# easyedainfo.net
KiCad netlist of a schematic drawn in EasyEDA
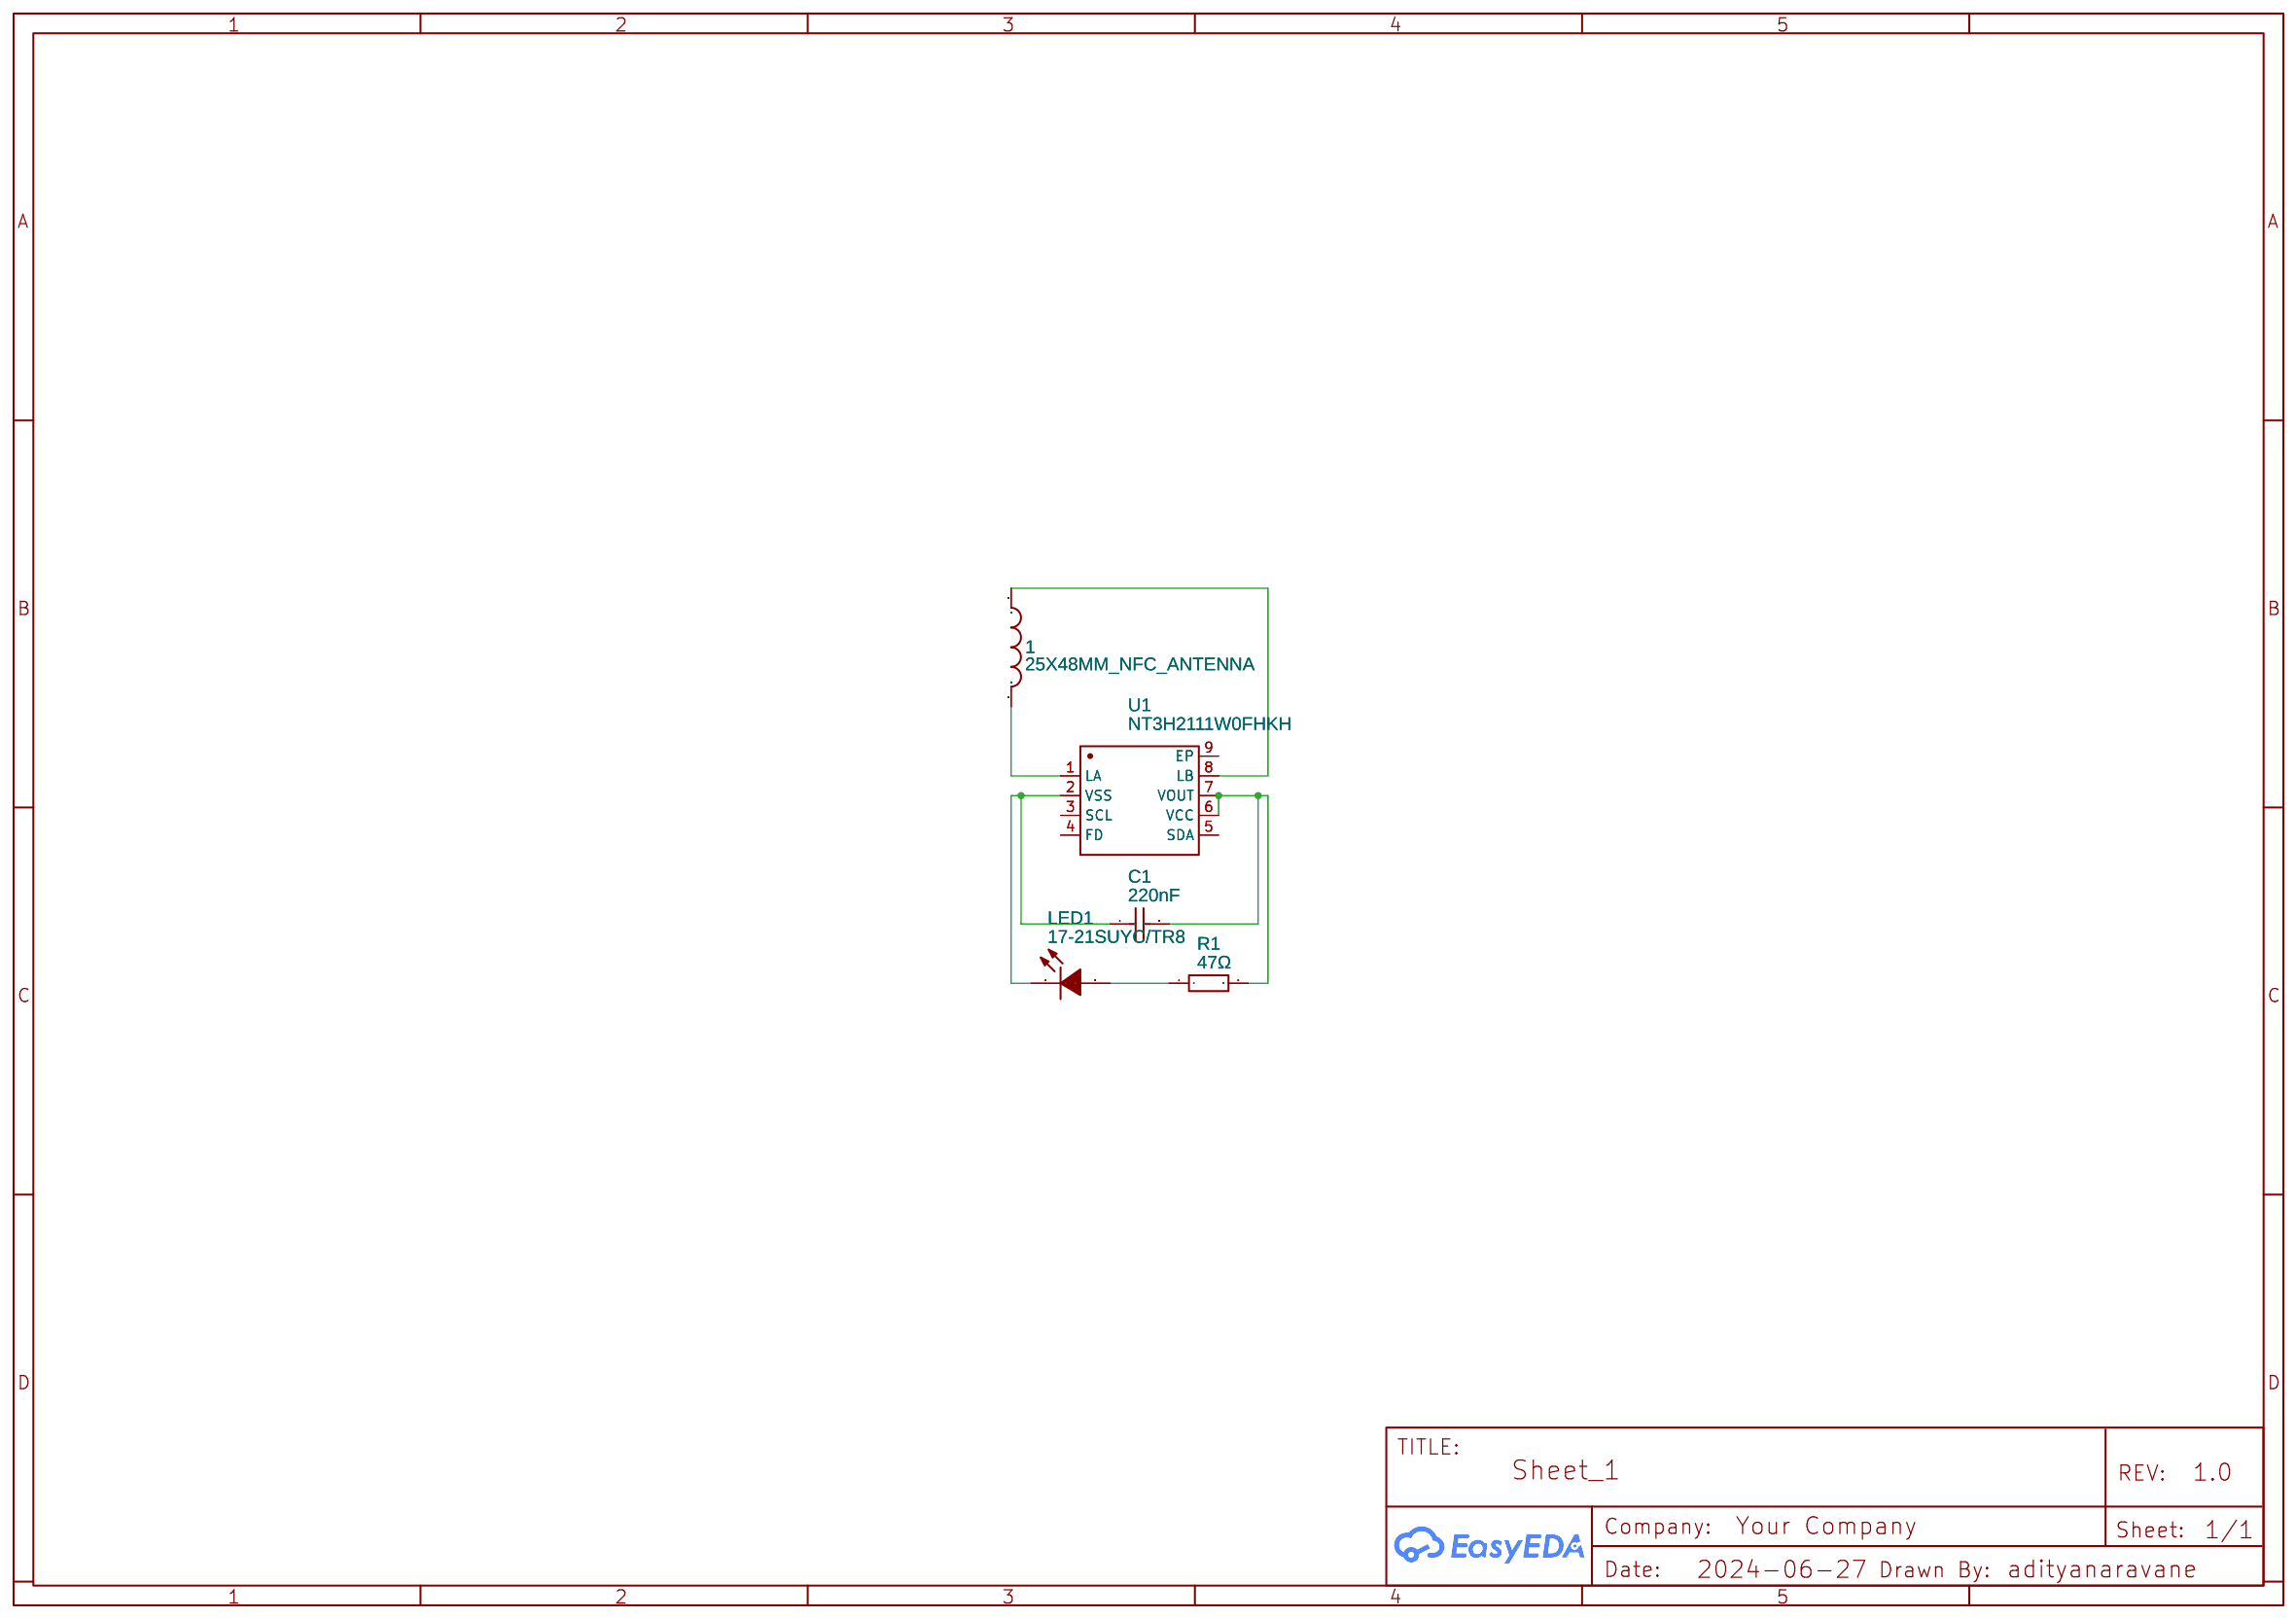
[diagram p0: schematic sheet]

(export (version "E")
  (design (tool "Eeschema 10.0.6"))
  (components
    (comp (ref "1") (value "25X48MM_NFC_ANTENNA") (libsource (lib "") (part "25X48MM_NFC_ANTENNA")))
    (comp (ref "C1")
      (value "220nF")
      (fields
        (field (name "Manufacturer Part") "CL10B224KA8NNNC")
        (field (name "Manufacturer") "SAMSUNG(三星)")
      )
      (libsource (lib "") (part "CL10B224KA8NNNC"))
    )
    (comp (ref "LED1")
      (value "17-21SUYC/TR8")
      (fields (field (name "Manufacturer Part") "KT-0805黄灯") (field (name "Manufacturer") "KENTO"))
      (libsource (lib "") (part "17-21SUYC/TR8"))
    )
    (comp (ref "R1")
      (value "47Ω")
      (fields
        (field (name "Manufacturer Part") "0603WAF470JT5E")
        (field (name "Manufacturer") "UNI-ROYAL(厚声)")
      )
      (libsource (lib "") (part "0603WAF470JT5E"))
    )
    (comp (ref "U1")
      (value "NT3H2111W0FHKH")
      (fields (field (name "Manufacturer") "NXP(恩智浦)"))
      (libsource (lib "") (part "NT3H2111W0FHKH"))
    )
  )
  (nets
    (net (code "1") (name "Net-(LED1-+)") (class "Default")
      (node (ref "LED1") (pin "1") (pinfunction "+_1") (pintype "unspecified"))
      (node (ref "R1") (pin "1") (pinfunction "1_1") (pintype "input"))
    )
    (net (code "2") (name "Net-(LED1--)") (class "Default")
      (node (ref "C1") (pin "1") (pinfunction "1_1") (pintype "input"))
      (node (ref "LED1") (pin "2") (pinfunction "-_2") (pintype "unspecified"))
      (node (ref "U1") (pin "2") (pinfunction "VSS_2") (pintype "unspecified"))
    )
    (net (code "3") (name "Net-(U1-LA)") (class "Default")
      (node (ref "1") (pin "P$2") (pinfunction "P$2_P$2") (pintype "bidirectional"))
      (node (ref "U1") (pin "1") (pinfunction "LA_1") (pintype "unspecified"))
    )
    (net (code "4") (name "Net-(U1-LB)") (class "Default")
      (node (ref "1") (pin "P$1") (pinfunction "P$1_P$1") (pintype "bidirectional"))
      (node (ref "U1") (pin "8") (pinfunction "LB_8") (pintype "unspecified"))
    )
    (net (code "5") (name "Net-(U1-VCC)") (class "Default")
      (node (ref "C1") (pin "2") (pinfunction "2_2") (pintype "input"))
      (node (ref "R1") (pin "2") (pinfunction "2_2") (pintype "input"))
      (node (ref "U1") (pin "6") (pinfunction "VCC_6") (pintype "unspecified"))
      (node (ref "U1") (pin "7") (pinfunction "VOUT_7") (pintype "unspecified"))
    )
    (net (code "6") (name "unconnected-(U1-EP-Pad9)") (class "Default")
      (node (ref "U1") (pin "9") (pinfunction "EP_9") (pintype "unspecified"))
    )
    (net (code "7") (name "unconnected-(U1-FD-Pad4)") (class "Default")
      (node (ref "U1") (pin "4") (pinfunction "FD_4") (pintype "unspecified"))
    )
    (net (code "8") (name "unconnected-(U1-SCL-Pad3)") (class "Default")
      (node (ref "U1") (pin "3") (pinfunction "SCL_3") (pintype "unspecified"))
    )
    (net (code "9") (name "unconnected-(U1-SDA-Pad5)") (class "Default")
      (node (ref "U1") (pin "5") (pinfunction "SDA_5") (pintype "unspecified"))
    )
  )
)
